# atmega_WS2812_RGB.net
KiCad netlist of a schematic drawn in EAGLE
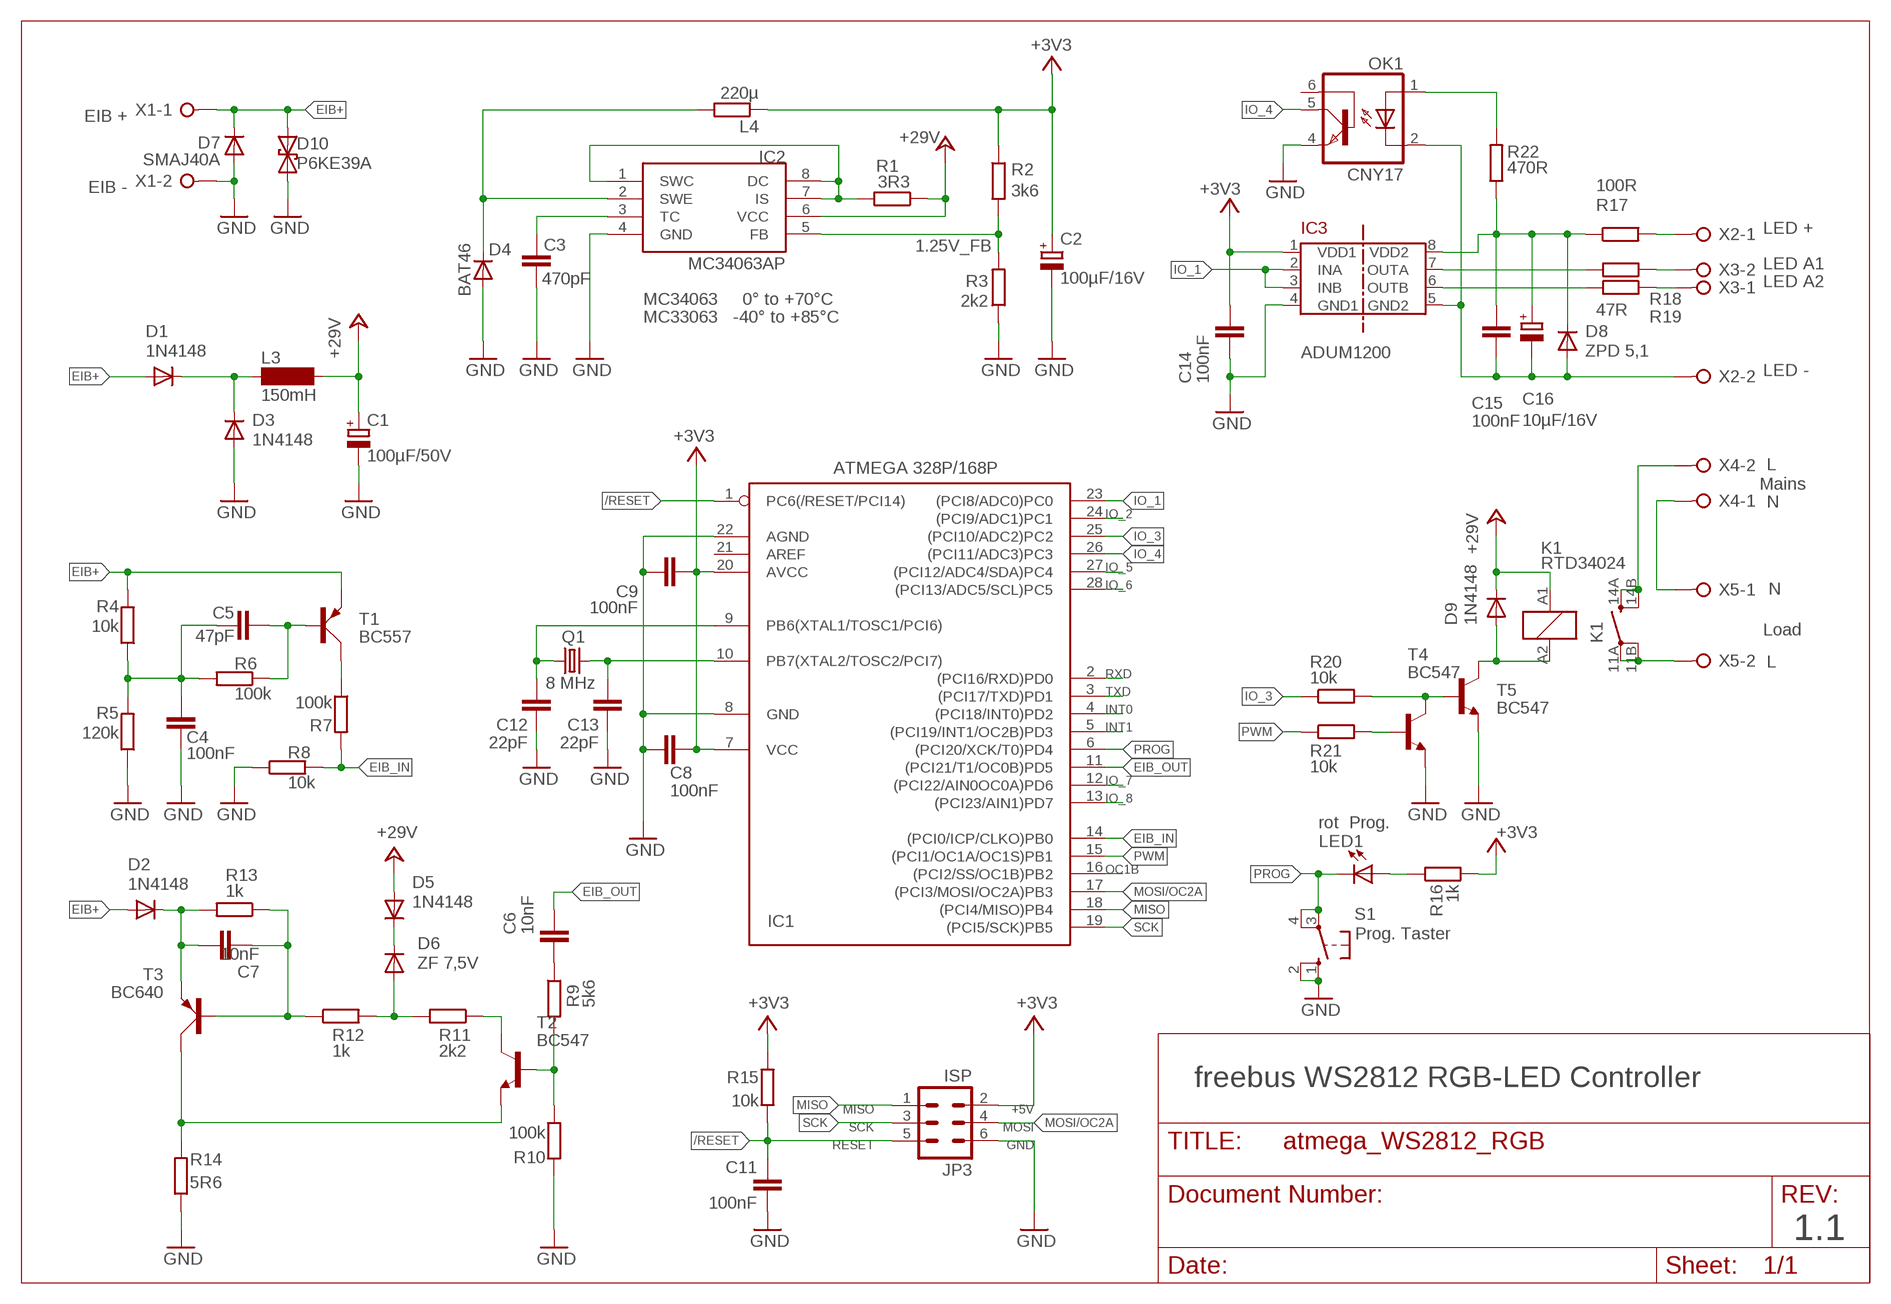
[diagram p0: schematic, sheet 1]

(export (version "E")
  (design (tool "Eeschema 10.0.6"))
  (components
    (comp (ref "C1")
      (value "100µF/50V")
      (footprint "eagle-import:E3,5-8")
      (libsource (lib "eagle-import") (part "CPOL-EUE3.5-8"))
    )
    (comp (ref "C2")
      (value "100µF/16V")
      (footprint "eagle-import:E3,5-8")
      (libsource (lib "eagle-import") (part "CPOL-EUE3.5-8"))
    )
    (comp (ref "C3")
      (value "470pF")
      (footprint "eagle-import:C025-024X044")
      (libsource (lib "eagle-import") (part "C-EU025-024X044"))
    )
    (comp (ref "C4")
      (value "100nF")
      (footprint "eagle-import:C025-024X044")
      (libsource (lib "eagle-import") (part "C-EU025-024X044"))
    )
    (comp (ref "C5")
      (value "47pF")
      (footprint "eagle-import:C025-024X044")
      (libsource (lib "eagle-import") (part "C-EU025-024X044"))
    )
    (comp (ref "C6")
      (value "10nF")
      (footprint "eagle-import:C025-024X044")
      (libsource (lib "eagle-import") (part "C-EU025-024X044"))
    )
    (comp (ref "C7")
      (value "10nF")
      (footprint "eagle-import:C025-024X044")
      (libsource (lib "eagle-import") (part "C-EU025-024X044"))
    )
    (comp (ref "C8")
      (value "100nF")
      (footprint "eagle-import:C025-024X044")
      (libsource (lib "eagle-import") (part "C-EU025-024X044"))
    )
    (comp (ref "C9")
      (value "100nF")
      (footprint "eagle-import:C025-024X044")
      (libsource (lib "eagle-import") (part "C-EU025-024X044"))
    )
    (comp (ref "C11")
      (value "100nF")
      (footprint "eagle-import:C025-024X044")
      (libsource (lib "eagle-import") (part "C-EU025-024X044"))
    )
    (comp (ref "C12")
      (value "22pF")
      (footprint "eagle-import:C025-024X044")
      (libsource (lib "eagle-import") (part "C-EU025-024X044"))
    )
    (comp (ref "C13")
      (value "22pF")
      (footprint "eagle-import:C025-024X044")
      (libsource (lib "eagle-import") (part "C-EU025-024X044"))
    )
    (comp (ref "C14")
      (value "100nF")
      (footprint "eagle-import:C025-024X044")
      (libsource (lib "eagle-import") (part "C-EU025-024X044"))
    )
    (comp (ref "C15")
      (value "100nF")
      (footprint "eagle-import:C025-024X044")
      (libsource (lib "eagle-import") (part "C-EU025-024X044"))
    )
    (comp (ref "C16")
      (value "10µF/16V")
      (footprint "eagle-import:E2-5")
      (libsource (lib "eagle-import") (part "CPOL-EUE2-5"))
    )
    (comp (ref "D1")
      (value "1N4148")
      (footprint "eagle-import:DO34-7R")
      (libsource (lib "eagle-import") (part "1N4148DO34-7R"))
    )
    (comp (ref "D2")
      (value "1N4148")
      (footprint "eagle-import:DO34-7R")
      (libsource (lib "eagle-import") (part "1N4148DO34-7R"))
    )
    (comp (ref "D3")
      (value "1N4148")
      (footprint "eagle-import:DO34-7R")
      (libsource (lib "eagle-import") (part "1N4148DO34-7R"))
    )
    (comp (ref "D4")
      (value "BAT46")
      (footprint "eagle-import:DO34-7R")
      (libsource (lib "eagle-import") (part "1N4148DO34-7R"))
    )
    (comp (ref "D5")
      (value "1N4148")
      (footprint "eagle-import:DO34-7R")
      (libsource (lib "eagle-import") (part "1N4148DO34-7R"))
    )
    (comp (ref "D6")
      (value "ZF 7,5V")
      (footprint "eagle-import:DO34-7R")
      (libsource (lib "eagle-import") (part "1N4148DO34-7R"))
    )
    (comp (ref "D7")
      (value "SMAJ40A")
      (footprint "eagle-import:SMB")
      (libsource (lib "eagle-import") (part "D-SMB"))
    )
    (comp (ref "D8")
      (value "ZPD 5,1")
      (footprint "eagle-import:DO34-7R")
      (libsource (lib "eagle-import") (part "1N4148DO34-7R"))
    )
    (comp (ref "D9")
      (value "1N4148")
      (footprint "eagle-import:DO34-7R")
      (libsource (lib "eagle-import") (part "1N4148DO34-7R"))
    )
    (comp (ref "D10")
      (value "P6KE39A")
      (footprint "eagle-import:DO41-7")
      (libsource (lib "eagle-import") (part "P6KEXXCDO41-7"))
    )
    (comp (ref "IC1")
      (value "ATMEGA 328P/168P")
      (footprint "eagle-import:DIL28-3")
      (libsource (lib "eagle-import") (part "ATMEGA168P-20"))
    )
    (comp (ref "IC2")
      (value "MC34063AP")
      (footprint "eagle-import:DIL08")
      (libsource (lib "eagle-import") (part "MC34063AP"))
    )
    (comp (ref "IC3")
      (value "ADUM1200")
      (footprint "eagle-import:SO8")
      (libsource (lib "eagle-import") (part "ADUM1200"))
    )
    (comp (ref "JP3")
      (value "ISP")
      (footprint "eagle-import:ML6")
      (libsource (lib "eagle-import") (part "ISP_6POLML6"))
    )
    (comp (ref "K1")
      (value "RTD34024")
      (footprint "eagle-import:RT-N_O16A5")
      (fields (field (name "MF") "TYCO ELECTRONICS") (field (name "MPN") "RTD34024F"))
      (libsource (lib "eagle-import") (part "RTD34024"))
    )
    (comp (ref "L3")
      (value "150mH")
      (footprint "eagle-import:BS11")
      (libsource (lib "eagle-import") (part "BS11"))
    )
    (comp (ref "L4")
      (value "220µ")
      (footprint "eagle-import:0309_12")
      (libsource (lib "eagle-import") (part "R-EU_0309/12"))
    )
    (comp (ref "LED1")
      (value "rot Prog.")
      (footprint "eagle-import:LED3MM")
      (libsource (lib "eagle-import") (part "LED3MM"))
    )
    (comp (ref "OK1")
      (value "CNY17")
      (footprint "eagle-import:DIL06")
      (fields (field (name "MPN") "CNY17-1"))
      (libsource (lib "eagle-import") (part "CNY17"))
    )
    (comp (ref "Q1")
      (value "8 MHz")
      (footprint "eagle-import:HC49U-V")
      (libsource (lib "eagle-import") (part "CRYSTALHC49U-V"))
    )
    (comp (ref "R1")
      (value "3R3")
      (footprint "eagle-import:0207_7")
      (libsource (lib "eagle-import") (part "R-EU_0207/7"))
    )
    (comp (ref "R2")
      (value "3k6")
      (footprint "eagle-import:0207_7")
      (libsource (lib "eagle-import") (part "R-EU_0207/7"))
    )
    (comp (ref "R3")
      (value "2k2")
      (footprint "eagle-import:0207_7")
      (libsource (lib "eagle-import") (part "R-EU_0207/7"))
    )
    (comp (ref "R4")
      (value "10k")
      (footprint "eagle-import:0207_7")
      (libsource (lib "eagle-import") (part "R-EU_0207/7"))
    )
    (comp (ref "R5")
      (value "120k")
      (footprint "eagle-import:0207_7")
      (libsource (lib "eagle-import") (part "R-EU_0207/7"))
    )
    (comp (ref "R6")
      (value "100k")
      (footprint "eagle-import:0207_7")
      (libsource (lib "eagle-import") (part "R-EU_0207/7"))
    )
    (comp (ref "R7")
      (value "100k")
      (footprint "eagle-import:0207_7")
      (libsource (lib "eagle-import") (part "R-EU_0207/7"))
    )
    (comp (ref "R8")
      (value "10k")
      (footprint "eagle-import:0207_7")
      (libsource (lib "eagle-import") (part "R-EU_0207/7"))
    )
    (comp (ref "R9")
      (value "5k6")
      (footprint "eagle-import:0207_7")
      (libsource (lib "eagle-import") (part "R-EU_0207/7"))
    )
    (comp (ref "R10")
      (value "100k")
      (footprint "eagle-import:0207_7")
      (libsource (lib "eagle-import") (part "R-EU_0207/7"))
    )
    (comp (ref "R11")
      (value "2k2")
      (footprint "eagle-import:0207_7")
      (libsource (lib "eagle-import") (part "R-EU_0207/7"))
    )
    (comp (ref "R12")
      (value "1k")
      (footprint "eagle-import:0207_7")
      (libsource (lib "eagle-import") (part "R-EU_0207/7"))
    )
    (comp (ref "R13")
      (value "1k")
      (footprint "eagle-import:0207_7")
      (libsource (lib "eagle-import") (part "R-EU_0207/7"))
    )
    (comp (ref "R14")
      (value "5R6")
      (footprint "eagle-import:0207_7")
      (libsource (lib "eagle-import") (part "R-EU_0207/7"))
    )
    (comp (ref "R15")
      (value "10k")
      (footprint "eagle-import:0207_7")
      (libsource (lib "eagle-import") (part "R-EU_0207/7"))
    )
    (comp (ref "R16")
      (value "1k")
      (footprint "eagle-import:0207_7")
      (libsource (lib "eagle-import") (part "R-EU_0207/7"))
    )
    (comp (ref "R17")
      (value "100R")
      (footprint "eagle-import:0207_7")
      (libsource (lib "eagle-import") (part "R-EU_0207/7"))
    )
    (comp (ref "R18")
      (value "47R")
      (footprint "eagle-import:0207_7")
      (libsource (lib "eagle-import") (part "R-EU_0207/7"))
    )
    (comp (ref "R19")
      (value "47R")
      (footprint "eagle-import:0207_7")
      (libsource (lib "eagle-import") (part "R-EU_0207/7"))
    )
    (comp (ref "R20")
      (value "10k")
      (footprint "eagle-import:0207_7")
      (libsource (lib "eagle-import") (part "R-EU_0207/7"))
    )
    (comp (ref "R21")
      (value "10k")
      (footprint "eagle-import:0207_7")
      (libsource (lib "eagle-import") (part "R-EU_0207/7"))
    )
    (comp (ref "R22")
      (value "470R")
      (footprint "eagle-import:0207_7")
      (libsource (lib "eagle-import") (part "R-EU_0207/7"))
    )
    (comp (ref "S1")
      (value "Prog. Taster")
      (footprint "eagle-import:B3F-10XX")
      (fields (field (name "MPN") "B3F-1000"))
      (libsource (lib "eagle-import") (part "10-XX"))
    )
    (comp (ref "T1")
      (value "BC557")
      (footprint "eagle-import:SOT54A")
      (libsource (lib "eagle-import") (part "BC557"))
    )
    (comp (ref "T2")
      (value "BC547")
      (footprint "eagle-import:TO92")
      (libsource (lib "eagle-import") (part "BC547"))
    )
    (comp (ref "T3")
      (value "BC640")
      (footprint "eagle-import:SOT54D")
      (libsource (lib "eagle-import") (part "BC640"))
    )
    (comp (ref "T4")
      (value "BC547")
      (footprint "eagle-import:TO92")
      (libsource (lib "eagle-import") (part "transistor-npn_BC547"))
    )
    (comp (ref "T5")
      (value "BC547")
      (footprint "eagle-import:TO92")
      (libsource (lib "eagle-import") (part "transistor-npn_BC547"))
    )
    (comp (ref "X1")
      (value "W237-02P")
      (footprint "eagle-import:W237-132")
      (libsource (lib "eagle-import") (part "W237-02P"))
    )
    (comp (ref "X2")
      (value "W237-02P")
      (footprint "eagle-import:W237-132")
      (libsource (lib "eagle-import") (part "W237-02P"))
    )
    (comp (ref "X3")
      (value "W237-02P")
      (footprint "eagle-import:W237-132")
      (libsource (lib "eagle-import") (part "W237-02P"))
    )
    (comp (ref "X4")
      (value "W237-02P")
      (footprint "eagle-import:W237-132")
      (libsource (lib "eagle-import") (part "W237-02P"))
    )
    (comp (ref "X5")
      (value "W237-02P")
      (footprint "eagle-import:W237-132")
      (libsource (lib "eagle-import") (part "W237-02P"))
    )
  )
  (nets
    (net (code "1") (name "+3V3") (class "Default")
      (node (ref "C14") (pin "2") (pinfunction "2_2") (pintype "passive"))
      (node (ref "C2") (pin "+") (pinfunction "+_+") (pintype "passive"))
      (node (ref "C8") (pin "1") (pinfunction "1_1") (pintype "passive"))
      (node (ref "C9") (pin "1") (pinfunction "1_1") (pintype "passive"))
      (node (ref "IC1") (pin "20") (pinfunction "AVCC_20") (pintype "bidirectional"))
      (node (ref "IC1") (pin "7") (pinfunction "VCC_7") (pintype "bidirectional"))
      (node (ref "IC3") (pin "1") (pinfunction "VDD1_1") (pintype "power_in"))
      (node (ref "JP3") (pin "2") (pinfunction "2_2") (pintype "passive"))
      (node (ref "L4") (pin "1") (pinfunction "1_1") (pintype "passive"))
      (node (ref "R15") (pin "2") (pinfunction "2_2") (pintype "passive"))
      (node (ref "R16") (pin "2") (pinfunction "2_2") (pintype "passive"))
      (node (ref "R2") (pin "1") (pinfunction "1_1") (pintype "passive"))
    )
    (net (code "2") (name "+29V") (class "Default")
      (node (ref "C1") (pin "+") (pinfunction "+_+") (pintype "passive"))
      (node (ref "D5") (pin "A") (pinfunction "A_A") (pintype "passive"))
      (node (ref "D9") (pin "C") (pinfunction "C_C") (pintype "passive"))
      (node (ref "IC2") (pin "6") (pinfunction "VCC_6") (pintype "passive"))
      (node (ref "K1") (pin "A1") (pinfunction "1_A1") (pintype "passive"))
      (node (ref "L3") (pin "2") (pinfunction "2_2") (pintype "passive"))
      (node (ref "R1") (pin "1") (pinfunction "1_1") (pintype "passive"))
    )
    (net (code "3") (name "/1.25V_FB") (class "Default")
      (node (ref "IC2") (pin "5") (pinfunction "FB_5") (pintype "passive"))
      (node (ref "R2") (pin "2") (pinfunction "2_2") (pintype "passive"))
      (node (ref "R3") (pin "2") (pinfunction "2_2") (pintype "passive"))
    )
    (net (code "4") (name "/INT0") (class "Default")
      (node (ref "IC1") (pin "4") (pinfunction "(PCI18/INT0)PD2_4") (pintype "bidirectional"))
    )
    (net (code "5") (name "/INT1") (class "Default")
      (node (ref "IC1") (pin "5") (pinfunction "(PCI19/INT1/OC2B)PD3_5") (pintype "bidirectional"))
    )
    (net (code "6") (name "/IO_2") (class "Default")
      (node (ref "IC1") (pin "24") (pinfunction "(PCI9/ADC1)PC1_24") (pintype "bidirectional"))
    )
    (net (code "7") (name "/IO_5") (class "Default")
      (node (ref "IC1") (pin "27") (pinfunction "(PCI12/ADC4/SDA)PC4_27") (pintype "bidirectional"))
    )
    (net (code "8") (name "/IO_6") (class "Default")
      (node (ref "IC1") (pin "28") (pinfunction "(PCI13/ADC5/SCL)PC5_28") (pintype "bidirectional"))
    )
    (net (code "9") (name "/IO_7") (class "Default")
      (node (ref "IC1") (pin "12") (pinfunction "(PCI22/AIN0OC0A)PD6_12") (pintype "bidirectional"))
    )
    (net (code "10") (name "/IO_8") (class "Default")
      (node (ref "IC1") (pin "13") (pinfunction "(PCI23/AIN1)PD7_13") (pintype "bidirectional"))
    )
    (net (code "11") (name "/OC1B") (class "Default")
      (node (ref "IC1") (pin "16") (pinfunction "(PCI2/SS/OC1B)PB2_16") (pintype "bidirectional"))
    )
    (net (code "12") (name "/RXD") (class "Default")
      (node (ref "IC1") (pin "2") (pinfunction "(PCI16/RXD)PD0_2") (pintype "bidirectional"))
    )
    (net (code "13") (name "/TXD") (class "Default")
      (node (ref "IC1") (pin "3") (pinfunction "(PCI17/TXD)PD1_3") (pintype "bidirectional"))
    )
    (net (code "14") (name "EIB+") (class "Default")
      (node (ref "D1") (pin "A") (pinfunction "A_A") (pintype "passive"))
      (node (ref "D10") (pin "C") (pinfunction "2_C") (pintype "passive"))
      (node (ref "D2") (pin "A") (pinfunction "A_A") (pintype "passive"))
      (node (ref "D7") (pin "1") (pinfunction "C_1") (pintype "passive"))
      (node (ref "R4") (pin "2") (pinfunction "2_2") (pintype "passive"))
      (node (ref "T1") (pin "E") (pinfunction "E_E") (pintype "passive"))
      (node (ref "X1") (pin "1") (pinfunction "KL_1") (pintype "passive"))
    )
    (net (code "15") (name "EIB_IN") (class "Default")
      (node (ref "IC1") (pin "14") (pinfunction "(PCI0/ICP/CLKO)PB0_14") (pintype "bidirectional"))
      (node (ref "R7") (pin "2") (pinfunction "2_2") (pintype "passive"))
      (node (ref "R8") (pin "2") (pinfunction "2_2") (pintype "passive"))
    )
    (net (code "16") (name "EIB_OUT") (class "Default")
      (node (ref "C6") (pin "2") (pinfunction "2_2") (pintype "passive"))
      (node (ref "IC1") (pin "11") (pinfunction "(PCI21/T1/OC0B)PD5_11") (pintype "bidirectional"))
    )
    (net (code "17") (name "GND") (class "Default")
      (node (ref "C1") (pin "-") (pinfunction "-_-") (pintype "passive"))
      (node (ref "C11") (pin "1") (pinfunction "1_1") (pintype "passive"))
      (node (ref "C12") (pin "2") (pinfunction "2_2") (pintype "passive"))
      (node (ref "C13") (pin "2") (pinfunction "2_2") (pintype "passive"))
      (node (ref "C14") (pin "1") (pinfunction "1_1") (pintype "passive"))
      (node (ref "C2") (pin "-") (pinfunction "-_-") (pintype "passive"))
      (node (ref "C3") (pin "1") (pinfunction "1_1") (pintype "passive"))
      (node (ref "C4") (pin "1") (pinfunction "1_1") (pintype "passive"))
      (node (ref "C8") (pin "2") (pinfunction "2_2") (pintype "passive"))
      (node (ref "C9") (pin "2") (pinfunction "2_2") (pintype "passive"))
      (node (ref "D10") (pin "A") (pinfunction "1_A") (pintype "passive"))
      (node (ref "D3") (pin "A") (pinfunction "A_A") (pintype "passive"))
      (node (ref "D4") (pin "A") (pinfunction "A_A") (pintype "passive"))
      (node (ref "D7") (pin "2") (pinfunction "A_2") (pintype "passive"))
      (node (ref "IC1") (pin "22") (pinfunction "AGND_22") (pintype "bidirectional"))
      (node (ref "IC1") (pin "8") (pinfunction "GND_8") (pintype "bidirectional"))
      (node (ref "IC2") (pin "4") (pinfunction "GND_4") (pintype "passive"))
      (node (ref "IC3") (pin "4") (pinfunction "GND1_4") (pintype "power_in"))
      (node (ref "JP3") (pin "6") (pinfunction "6_6") (pintype "passive"))
      (node (ref "OK1") (pin "4") (pinfunction "EMI_4") (pintype "passive"))
      (node (ref "R10") (pin "2") (pinfunction "2_2") (pintype "passive"))
      (node (ref "R14") (pin "1") (pinfunction "1_1") (pintype "passive"))
      (node (ref "R3") (pin "1") (pinfunction "1_1") (pintype "passive"))
      (node (ref "R5") (pin "1") (pinfunction "1_1") (pintype "passive"))
      (node (ref "R8") (pin "1") (pinfunction "1_1") (pintype "passive"))
      (node (ref "S1") (pin "1") (pinfunction "S_1") (pintype "passive"))
      (node (ref "S1") (pin "2") (pinfunction "S1_2") (pintype "passive"))
      (node (ref "T4") (pin "1") (pinfunction "E_1") (pintype "passive"))
      (node (ref "T5") (pin "1") (pinfunction "E_1") (pintype "passive"))
      (node (ref "X1") (pin "2") (pinfunction "KL_2") (pintype "passive"))
    )
    (net (code "18") (name "IO_1") (class "Default")
      (node (ref "IC1") (pin "23") (pinfunction "(PCI8/ADC0)PC0_23") (pintype "bidirectional"))
      (node (ref "IC3") (pin "2") (pinfunction "INA_2") (pintype "input"))
      (node (ref "IC3") (pin "3") (pinfunction "INB_3") (pintype "input"))
    )
    (net (code "19") (name "IO_3") (class "Default")
      (node (ref "IC1") (pin "25") (pinfunction "(PCI10/ADC2)PC2_25") (pintype "bidirectional"))
      (node (ref "R20") (pin "1") (pinfunction "1_1") (pintype "passive"))
    )
    (net (code "20") (name "IO_4") (class "Default")
      (node (ref "IC1") (pin "26") (pinfunction "(PCI11/ADC3)PC3_26") (pintype "bidirectional"))
      (node (ref "OK1") (pin "5") (pinfunction "COL_5") (pintype "passive"))
    )
    (net (code "21") (name "MISO") (class "Default")
      (node (ref "IC1") (pin "18") (pinfunction "(PCI4/MISO)PB4_18") (pintype "bidirectional"))
      (node (ref "JP3") (pin "1") (pinfunction "1_1") (pintype "passive"))
    )
    (net (code "22") (name "MOSI{slash}OC2A") (class "Default")
      (node (ref "IC1") (pin "17") (pinfunction "(PCI3/MOSI/OC2A)PB3_17") (pintype "bidirectional"))
      (node (ref "JP3") (pin "4") (pinfunction "4_4") (pintype "passive"))
    )
    (net (code "23") (name "Net-(C4-Pad2)") (class "Default")
      (node (ref "C4") (pin "2") (pinfunction "2_2") (pintype "passive"))
      (node (ref "C5") (pin "1") (pinfunction "1_1") (pintype "passive"))
      (node (ref "R4") (pin "1") (pinfunction "1_1") (pintype "passive"))
      (node (ref "R5") (pin "2") (pinfunction "2_2") (pintype "passive"))
      (node (ref "R6") (pin "2") (pinfunction "2_2") (pintype "passive"))
    )
    (net (code "24") (name "Net-(C5-Pad2)") (class "Default")
      (node (ref "C5") (pin "2") (pinfunction "2_2") (pintype "passive"))
      (node (ref "R6") (pin "1") (pinfunction "1_1") (pintype "passive"))
      (node (ref "T1") (pin "B") (pinfunction "B_B") (pintype "passive"))
    )
    (net (code "25") (name "Net-(C6-Pad1)") (class "Default")
      (node (ref "C6") (pin "1") (pinfunction "1_1") (pintype "passive"))
      (node (ref "R9") (pin "1") (pinfunction "1_1") (pintype "passive"))
    )
    (net (code "26") (name "Net-(C7-Pad1)") (class "Default")
      (node (ref "C7") (pin "1") (pinfunction "1_1") (pintype "passive"))
      (node (ref "D2") (pin "C") (pinfunction "C_C") (pintype "passive"))
      (node (ref "R13") (pin "2") (pinfunction "2_2") (pintype "passive"))
      (node (ref "T3") (pin "E") (pinfunction "E_E") (pintype "passive"))
    )
    (net (code "27") (name "Net-(C7-Pad2)") (class "Default")
      (node (ref "C7") (pin "2") (pinfunction "2_2") (pintype "passive"))
      (node (ref "R12") (pin "1") (pinfunction "1_1") (pintype "passive"))
      (node (ref "R13") (pin "1") (pinfunction "1_1") (pintype "passive"))
      (node (ref "T3") (pin "B") (pinfunction "B_B") (pintype "passive"))
    )
    (net (code "28") (name "Net-(D1-PadC)") (class "Default")
      (node (ref "D1") (pin "C") (pinfunction "C_C") (pintype "passive"))
      (node (ref "D3") (pin "C") (pinfunction "C_C") (pintype "passive"))
      (node (ref "L3") (pin "1") (pinfunction "1_1") (pintype "passive"))
    )
    (net (code "29") (name "Net-(D5-PadC)") (class "Default")
      (node (ref "D5") (pin "C") (pinfunction "C_C") (pintype "passive"))
      (node (ref "D6") (pin "C") (pinfunction "C_C") (pintype "passive"))
    )
    (net (code "30") (name "Net-(D6-PadA)") (class "Default")
      (node (ref "D6") (pin "A") (pinfunction "A_A") (pintype "passive"))
      (node (ref "R11") (pin "2") (pinfunction "2_2") (pintype "passive"))
      (node (ref "R12") (pin "2") (pinfunction "2_2") (pintype "passive"))
    )
    (net (code "31") (name "Net-(IC1-PB6(XTAL1{slash}TOSC1{slash}PCI6))") (class "Default")
      (node (ref "C12") (pin "1") (pinfunction "1_1") (pintype "passive"))
      (node (ref "IC1") (pin "9") (pinfunction "PB6(XTAL1/TOSC1/PCI6)_9") (pintype "bidirectional"))
      (node (ref "Q1") (pin "1") (pinfunction "1_1") (pintype "passive"))
    )
    (net (code "32") (name "Net-(IC1-PB7(XTAL2{slash}TOSC2{slash}PCI7))") (class "Default")
      (node (ref "C13") (pin "1") (pinfunction "1_1") (pintype "passive"))
      (node (ref "IC1") (pin "10") (pinfunction "PB7(XTAL2/TOSC2/PCI7)_10") (pintype "bidirectional"))
      (node (ref "Q1") (pin "2") (pinfunction "2_2") (pintype "passive"))
    )
    (net (code "33") (name "Net-(IC2-DC)") (class "Default")
      (node (ref "IC2") (pin "1") (pinfunction "SWC_1") (pintype "passive"))
      (node (ref "IC2") (pin "7") (pinfunction "IS_7") (pintype "passive"))
      (node (ref "IC2") (pin "8") (pinfunction "DC_8") (pintype "passive"))
      (node (ref "R1") (pin "2") (pinfunction "2_2") (pintype "passive"))
    )
    (net (code "34") (name "Net-(IC2-SWE)") (class "Default")
      (node (ref "D4") (pin "C") (pinfunction "C_C") (pintype "passive"))
      (node (ref "IC2") (pin "2") (pinfunction "SWE_2") (pintype "passive"))
      (node (ref "L4") (pin "2") (pinfunction "2_2") (pintype "passive"))
    )
    (net (code "35") (name "Net-(IC2-TC)") (class "Default")
      (node (ref "C3") (pin "2") (pinfunction "2_2") (pintype "passive"))
      (node (ref "IC2") (pin "3") (pinfunction "TC_3") (pintype "passive"))
    )
    (net (code "36") (name "Net-(IC3-GND2)") (class "Default")
      (node (ref "C15") (pin "1") (pinfunction "1_1") (pintype "passive"))
      (node (ref "C16") (pin "-") (pinfunction "-_-") (pintype "passive"))
      (node (ref "D8") (pin "A") (pinfunction "A_A") (pintype "passive"))
      (node (ref "IC3") (pin "5") (pinfunction "GND2_5") (pintype "power_in"))
      (node (ref "OK1") (pin "2") (pinfunction "C_2") (pintype "passive"))
      (node (ref "X2") (pin "2") (pinfunction "KL_2") (pintype "passive"))
    )
    (net (code "37") (name "Net-(IC3-OUTA)") (class "Default")
      (node (ref "IC3") (pin "7") (pinfunction "OUTA_7") (pintype "output"))
      (node (ref "R18") (pin "2") (pinfunction "2_2") (pintype "passive"))
    )
    (net (code "38") (name "Net-(IC3-OUTB)") (class "Default")
      (node (ref "IC3") (pin "6") (pinfunction "OUTB_6") (pintype "output"))
      (node (ref "R19") (pin "2") (pinfunction "2_2") (pintype "passive"))
    )
    (net (code "39") (name "Net-(IC3-VDD2)") (class "Default")
      (node (ref "C15") (pin "2") (pinfunction "2_2") (pintype "passive"))
      (node (ref "C16") (pin "+") (pinfunction "+_+") (pintype "passive"))
      (node (ref "D8") (pin "C") (pinfunction "C_C") (pintype "passive"))
      (node (ref "IC3") (pin "8") (pinfunction "VDD2_8") (pintype "power_in"))
      (node (ref "R17") (pin "1") (pinfunction "1_1") (pintype "passive"))
      (node (ref "R22") (pin "1") (pinfunction "1_1") (pintype "passive"))
    )
    (net (code "40") (name "Net-(K1A-2)") (class "Default")
      (node (ref "D9") (pin "A") (pinfunction "A_A") (pintype "passive"))
      (node (ref "K1") (pin "A2") (pinfunction "2_A2") (pintype "passive"))
      (node (ref "T5") (pin "3") (pinfunction "C_3") (pintype "passive"))
    )
    (net (code "41") (name "Net-(K1B-PA)") (class "Default")
      (node (ref "K1") (pin "11A") (pinfunction "PA_11A") (pintype "passive"))
      (node (ref "K1") (pin "11B") (pinfunction "PB_11B") (pintype "passive"))
      (node (ref "X5") (pin "2") (pinfunction "KL_2") (pintype "passive"))
    )
    (net (code "42") (name "Net-(K1B-SA)") (class "Default")
      (node (ref "K1") (pin "14A") (pinfunction "SA_14A") (pintype "passive"))
      (node (ref "K1") (pin "14B") (pinfunction "SB_14B") (pintype "passive"))
      (node (ref "X4") (pin "2") (pinfunction "KL_2") (pintype "passive"))
    )
    (net (code "43") (name "Net-(LED1-PadA)") (class "Default")
      (node (ref "LED1") (pin "A") (pinfunction "A_A") (pintype "passive"))
      (node (ref "R16") (pin "1") (pinfunction "1_1") (pintype "passive"))
    )
    (net (code "44") (name "Net-(OK1-A)") (class "Default")
      (node (ref "OK1") (pin "1") (pinfunction "A_1") (pintype "passive"))
      (node (ref "R22") (pin "2") (pinfunction "2_2") (pintype "passive"))
    )
    (net (code "45") (name "Net-(R7-Pad1)") (class "Default")
      (node (ref "R7") (pin "1") (pinfunction "1_1") (pintype "passive"))
      (node (ref "T1") (pin "C") (pinfunction "C_C") (pintype "passive"))
    )
    (net (code "46") (name "Net-(T2-B)") (class "Default")
      (node (ref "R10") (pin "1") (pinfunction "1_1") (pintype "passive"))
      (node (ref "R9") (pin "2") (pinfunction "2_2") (pintype "passive"))
      (node (ref "T2") (pin "2") (pinfunction "B_2") (pintype "passive"))
    )
    (net (code "47") (name "Net-(T2-C)") (class "Default")
      (node (ref "R11") (pin "1") (pinfunction "1_1") (pintype "passive"))
      (node (ref "T2") (pin "3") (pinfunction "C_3") (pintype "passive"))
    )
    (net (code "48") (name "Net-(T2-E)") (class "Default")
      (node (ref "R14") (pin "2") (pinfunction "2_2") (pintype "passive"))
      (node (ref "T2") (pin "1") (pinfunction "E_1") (pintype "passive"))
      (node (ref "T3") (pin "C") (pinfunction "C_C") (pintype "passive"))
    )
    (net (code "49") (name "Net-(T4-B)") (class "Default")
      (node (ref "R21") (pin "2") (pinfunction "2_2") (pintype "passive"))
      (node (ref "T4") (pin "2") (pinfunction "B_2") (pintype "passive"))
    )
    (net (code "50") (name "Net-(T4-C)") (class "Default")
      (node (ref "R20") (pin "2") (pinfunction "2_2") (pintype "passive"))
      (node (ref "T4") (pin "3") (pinfunction "C_3") (pintype "passive"))
      (node (ref "T5") (pin "2") (pinfunction "B_2") (pintype "passive"))
    )
    (net (code "51") (name "Net-(X2A-KL)") (class "Default")
      (node (ref "R17") (pin "2") (pinfunction "2_2") (pintype "passive"))
      (node (ref "X2") (pin "1") (pinfunction "KL_1") (pintype "passive"))
    )
    (net (code "52") (name "Net-(X3A-KL)") (class "Default")
      (node (ref "R19") (pin "1") (pinfunction "1_1") (pintype "passive"))
      (node (ref "X3") (pin "1") (pinfunction "KL_1") (pintype "passive"))
    )
    (net (code "53") (name "Net-(X3B-KL)") (class "Default")
      (node (ref "R18") (pin "1") (pinfunction "1_1") (pintype "passive"))
      (node (ref "X3") (pin "2") (pinfunction "KL_2") (pintype "passive"))
    )
    (net (code "54") (name "Net-(X4A-KL)") (class "Default")
      (node (ref "X4") (pin "1") (pinfunction "KL_1") (pintype "passive"))
      (node (ref "X5") (pin "1") (pinfunction "KL_1") (pintype "passive"))
    )
    (net (code "55") (name "PROG") (class "Default")
      (node (ref "IC1") (pin "6") (pinfunction "(PCI20/XCK/T0)PD4_6") (pintype "bidirectional"))
      (node (ref "LED1") (pin "K") (pinfunction "C_K") (pintype "passive"))
      (node (ref "S1") (pin "3") (pinfunction "P_3") (pintype "passive"))
      (node (ref "S1") (pin "4") (pinfunction "P1_4") (pintype "passive"))
    )
    (net (code "56") (name "PWM") (class "Default")
      (node (ref "IC1") (pin "15") (pinfunction "(PCI1/OC1A/OC1S)PB1_15") (pintype "bidirectional"))
      (node (ref "R21") (pin "1") (pinfunction "1_1") (pintype "passive"))
    )
    (net (code "57") (name "SCK") (class "Default")
      (node (ref "IC1") (pin "19") (pinfunction "(PCI5/SCK)PB5_19") (pintype "bidirectional"))
      (node (ref "JP3") (pin "3") (pinfunction "3_3") (pintype "passive"))
    )
    (net (code "58") (name "unconnected-(IC1-AREF-Pad21)") (class "Default")
      (node (ref "IC1") (pin "21") (pinfunction "AREF_21") (pintype "bidirectional"))
    )
    (net (code "59") (name "unconnected-(OK1-BAS-Pad6)") (class "Default")
      (node (ref "OK1") (pin "6") (pinfunction "BAS_6") (pintype "passive"))
    )
    (net (code "60") (name "{slash}RESET") (class "Default")
      (node (ref "C11") (pin "2") (pinfunction "2_2") (pintype "passive"))
      (node (ref "IC1") (pin "1") (pinfunction "PC6(/RESET/PCI14)_1") (pintype "bidirectional"))
      (node (ref "JP3") (pin "5") (pinfunction "5_5") (pintype "passive"))
      (node (ref "R15") (pin "1") (pinfunction "1_1") (pintype "passive"))
    )
  )
)
